# ACK_2_Sheet6.net
KiCad netlist of a schematic drawn in Altium Designer
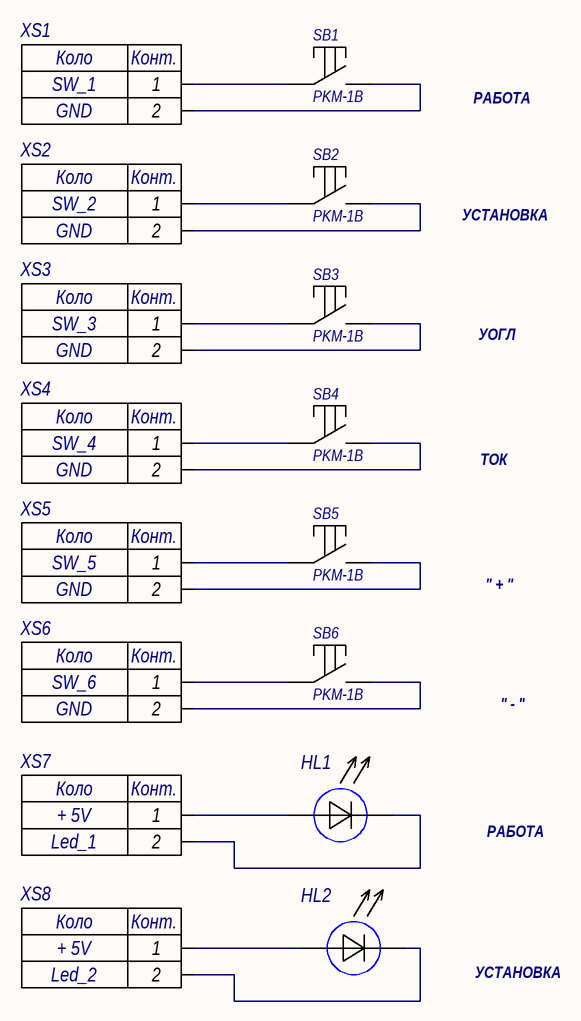
[diagram p0: ACK_2_Sheet6.SchDoc]

(export (version "E")
  (design (tool "Eeschema 10.0.6"))
  (components
    (comp (ref "HL1") (value "LED_1") (footprint "LED_VISHAY_VLMX1") (libsource (lib "АСК_1") (part "LED_1")))
    (comp (ref "HL2") (value "LED_1") (footprint "LED_VISHAY_VLMX1") (libsource (lib "АСК_1") (part "LED_1")))
    (comp (ref "SB1") (value "PKM-1B") (libsource (lib "АСК_1") (part "PKM-1B")))
    (comp (ref "SB2") (value "PKM-1B") (libsource (lib "АСК_1") (part "PKM-1B")))
    (comp (ref "SB3") (value "PKM-1B") (libsource (lib "АСК_1") (part "PKM-1B")))
    (comp (ref "SB4") (value "PKM-1B") (libsource (lib "АСК_1") (part "PKM-1B")))
    (comp (ref "SB5") (value "PKM-1B") (libsource (lib "АСК_1") (part "PKM-1B")))
    (comp (ref "SB6") (value "PKM-1B") (libsource (lib "АСК_1") (part "PKM-1B")))
    (comp (ref "XS1") (value "M20-9770242") (libsource (lib "АСК_1") (part "M20-9770242")))
    (comp (ref "XS2") (value "M20-9770242") (libsource (lib "АСК_1") (part "M20-9770242")))
    (comp (ref "XS3") (value "M20-9770242") (libsource (lib "АСК_1") (part "M20-9770242")))
    (comp (ref "XS4") (value "M20-9770242") (libsource (lib "АСК_1") (part "M20-9770242")))
    (comp (ref "XS5") (value "M20-9770242") (libsource (lib "АСК_1") (part "M20-9770242")))
    (comp (ref "XS6") (value "M20-9770242") (libsource (lib "АСК_1") (part "M20-9770242")))
    (comp (ref "XS7") (value "M20-9770242") (libsource (lib "АСК_1") (part "M20-9770242")))
    (comp (ref "XS8") (value "M20-9770242") (libsource (lib "АСК_1") (part "M20-9770242")))
  )
  (nets
    (net (code "1") (name "Net-(HL1-Pad1)") (class "Default")
      (node (ref "HL1") (pin "1") (pinfunction "1_1") (pintype "passive"))
      (node (ref "XS7") (pin "1") (pinfunction "1_1") (pintype "passive"))
    )
    (net (code "2") (name "Net-(HL1-Pad2)") (class "Default")
      (node (ref "HL1") (pin "2") (pinfunction "2_2") (pintype "passive"))
      (node (ref "XS7") (pin "2") (pinfunction "2_2") (pintype "passive"))
    )
    (net (code "3") (name "Net-(HL2-Pad1)") (class "Default")
      (node (ref "HL2") (pin "1") (pinfunction "1_1") (pintype "passive"))
      (node (ref "XS8") (pin "1") (pinfunction "1_1") (pintype "passive"))
    )
    (net (code "4") (name "Net-(HL2-Pad2)") (class "Default")
      (node (ref "HL2") (pin "2") (pinfunction "2_2") (pintype "passive"))
      (node (ref "XS8") (pin "2") (pinfunction "2_2") (pintype "passive"))
    )
    (net (code "5") (name "Net-(SB1-Pad1)") (class "Default")
      (node (ref "SB1") (pin "1") (pinfunction "1_1") (pintype "passive"))
      (node (ref "XS1") (pin "1") (pinfunction "1_1") (pintype "passive"))
    )
    (net (code "6") (name "Net-(SB1-Pad2)") (class "Default")
      (node (ref "SB1") (pin "2") (pinfunction "2_2") (pintype "passive"))
      (node (ref "XS1") (pin "2") (pinfunction "2_2") (pintype "passive"))
    )
    (net (code "7") (name "Net-(SB2-Pad1)") (class "Default")
      (node (ref "SB2") (pin "1") (pinfunction "1_1") (pintype "passive"))
      (node (ref "XS2") (pin "1") (pinfunction "1_1") (pintype "passive"))
    )
    (net (code "8") (name "Net-(SB2-Pad2)") (class "Default")
      (node (ref "SB2") (pin "2") (pinfunction "2_2") (pintype "passive"))
      (node (ref "XS2") (pin "2") (pinfunction "2_2") (pintype "passive"))
    )
    (net (code "9") (name "Net-(SB3-Pad1)") (class "Default")
      (node (ref "SB3") (pin "1") (pinfunction "1_1") (pintype "passive"))
      (node (ref "XS3") (pin "1") (pinfunction "1_1") (pintype "passive"))
    )
    (net (code "10") (name "Net-(SB3-Pad2)") (class "Default")
      (node (ref "SB3") (pin "2") (pinfunction "2_2") (pintype "passive"))
      (node (ref "XS3") (pin "2") (pinfunction "2_2") (pintype "passive"))
    )
    (net (code "11") (name "Net-(SB4-Pad1)") (class "Default")
      (node (ref "SB4") (pin "1") (pinfunction "1_1") (pintype "passive"))
      (node (ref "XS4") (pin "1") (pinfunction "1_1") (pintype "passive"))
    )
    (net (code "12") (name "Net-(SB4-Pad2)") (class "Default")
      (node (ref "SB4") (pin "2") (pinfunction "2_2") (pintype "passive"))
      (node (ref "XS4") (pin "2") (pinfunction "2_2") (pintype "passive"))
    )
    (net (code "13") (name "Net-(SB5-Pad1)") (class "Default")
      (node (ref "SB5") (pin "1") (pinfunction "1_1") (pintype "passive"))
      (node (ref "XS5") (pin "1") (pinfunction "1_1") (pintype "passive"))
    )
    (net (code "14") (name "Net-(SB5-Pad2)") (class "Default")
      (node (ref "SB5") (pin "2") (pinfunction "2_2") (pintype "passive"))
      (node (ref "XS5") (pin "2") (pinfunction "2_2") (pintype "passive"))
    )
    (net (code "15") (name "Net-(SB6-Pad1)") (class "Default")
      (node (ref "SB6") (pin "1") (pinfunction "1_1") (pintype "passive"))
      (node (ref "XS6") (pin "1") (pinfunction "1_1") (pintype "passive"))
    )
    (net (code "16") (name "Net-(SB6-Pad2)") (class "Default")
      (node (ref "SB6") (pin "2") (pinfunction "2_2") (pintype "passive"))
      (node (ref "XS6") (pin "2") (pinfunction "2_2") (pintype "passive"))
    )
  )
)
